# cheapboard1_0.net
KiCad netlist of a schematic drawn in EAGLE
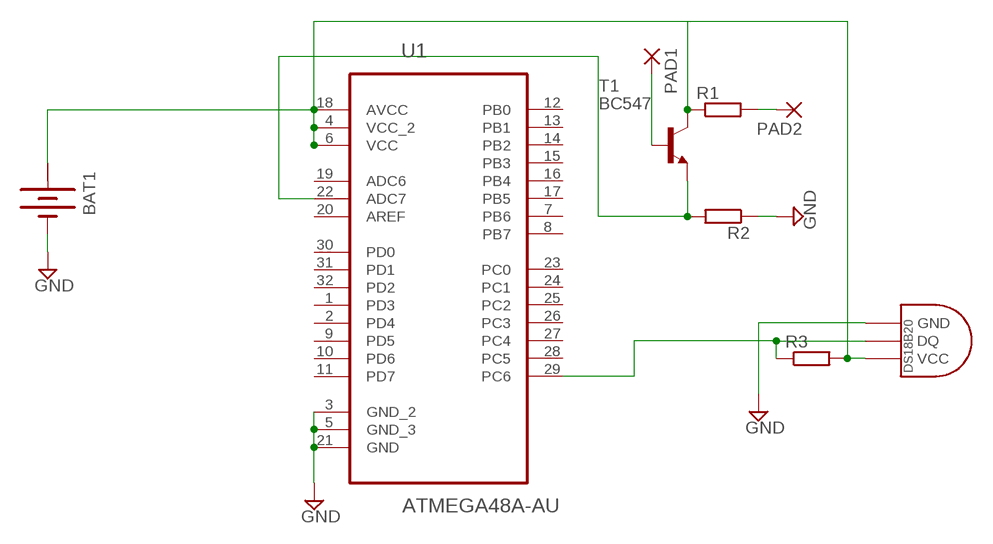
[diagram p0: schematic, sheet 1]

(export (version "E")
  (design (tool "Eeschema 10.0.6"))
  (components
    (comp (ref "BAT1")
      (value "BATTERY")
      (footprint "eagle-import:BATTERY")
      (libsource (lib "eagle-import") (part "BATTERY"))
    )
    (comp (ref "PAD1")
      (value "SMD5")
      (footprint "eagle-import:SMD2,54-5,08")
      (libsource (lib "eagle-import") (part "SMD5"))
    )
    (comp (ref "PAD2")
      (value "SMD5")
      (footprint "eagle-import:SMD2,54-5,08")
      (libsource (lib "eagle-import") (part "SMD5"))
    )
    (comp (ref "R1")
      (value "R-EU_M0805")
      (footprint "eagle-import:M0805")
      (libsource (lib "eagle-import") (part "R-EU_M0805"))
    )
    (comp (ref "R2")
      (value "R-EU_M0805")
      (footprint "eagle-import:M0805")
      (libsource (lib "eagle-import") (part "R-EU_M0805"))
    )
    (comp (ref "R3")
      (value "R-EU_M0805")
      (footprint "eagle-import:M0805")
      (libsource (lib "eagle-import") (part "R-EU_M0805"))
    )
    (comp (ref "T1")
      (value "BC547")
      (footprint "eagle-import:TO92")
      (libsource (lib "eagle-import") (part "BC547"))
    )
    (comp (ref "U$1")
      (value "DS1820SOIC")
      (footprint "eagle-import:DS18B20_SOIC")
      (libsource (lib "eagle-import") (part "DS1820SOIC"))
    )
    (comp (ref "U1")
      (value "ATMEGA48A-AU")
      (footprint "eagle-import:QFP80P900X900X120-32N")
      (libsource (lib "eagle-import") (part "ATMEGA48A-AU"))
    )
  )
  (nets
    (net (code "1") (name "/+") (class "Default")
      (node (ref "BAT1") (pin "+@1") (pinfunction "+_+@1") (pintype "power_in"))
    )
    (net (code "2") (name "GND") (class "Default")
      (node (ref "BAT1") (pin "-") (pinfunction "-_-") (pintype "power_in"))
      (node (ref "R2") (pin "1") (pinfunction "1_1") (pintype "passive"))
      (node (ref "U$1") (pin "GND") (pinfunction "GND_GND") (pintype "power_in"))
      (node (ref "U1") (pin "21") (pinfunction "GND_21") (pintype "passive"))
      (node (ref "U1") (pin "3") (pinfunction "GND_2_3") (pintype "passive"))
      (node (ref "U1") (pin "5") (pinfunction "GND_3_5") (pintype "passive"))
    )
    (net (code "3") (name "Net-(PAD1-P)") (class "Default")
      (node (ref "PAD1") (pin "1") (pinfunction "P_1") (pintype "passive"))
      (node (ref "T1") (pin "2") (pinfunction "B_2") (pintype "passive"))
    )
    (net (code "4") (name "Net-(PAD2-P)") (class "Default")
      (node (ref "PAD2") (pin "1") (pinfunction "P_1") (pintype "passive"))
      (node (ref "R1") (pin "2") (pinfunction "2_2") (pintype "passive"))
    )
    (net (code "5") (name "Net-(T1-C)") (class "Default")
      (node (ref "BAT1") (pin "+") (pinfunction "+_+") (pintype "power_in"))
      (node (ref "R1") (pin "1") (pinfunction "1_1") (pintype "passive"))
      (node (ref "R3") (pin "2") (pinfunction "2_2") (pintype "passive"))
      (node (ref "T1") (pin "3") (pinfunction "C_3") (pintype "passive"))
      (node (ref "U$1") (pin "VCC") (pinfunction "VCC_VCC") (pintype "power_in"))
      (node (ref "U1") (pin "18") (pinfunction "AVCC_18") (pintype "power_in"))
      (node (ref "U1") (pin "4") (pinfunction "VCC_2_4") (pintype "power_in"))
      (node (ref "U1") (pin "6") (pinfunction "VCC_6") (pintype "power_in"))
    )
    (net (code "6") (name "Net-(T1-E)") (class "Default")
      (node (ref "R2") (pin "2") (pinfunction "2_2") (pintype "passive"))
      (node (ref "T1") (pin "1") (pinfunction "E_1") (pintype "passive"))
      (node (ref "U1") (pin "22") (pinfunction "ADC7_22") (pintype "input"))
    )
    (net (code "7") (name "Net-(U1-PC6)") (class "Default")
      (node (ref "R3") (pin "1") (pinfunction "1_1") (pintype "passive"))
      (node (ref "U$1") (pin "DQ") (pinfunction "DQ_DQ") (pintype "bidirectional"))
      (node (ref "U1") (pin "29") (pinfunction "PC6_29") (pintype "bidirectional"))
    )
    (net (code "8") (name "unconnected-(U1-ADC6-Pad19)") (class "Default")
      (node (ref "U1") (pin "19") (pinfunction "ADC6_19") (pintype "input"))
    )
    (net (code "9") (name "unconnected-(U1-AREF-Pad20)") (class "Default")
      (node (ref "U1") (pin "20") (pinfunction "AREF_20") (pintype "input"))
    )
    (net (code "10") (name "unconnected-(U1-PB0-Pad12)") (class "Default")
      (node (ref "U1") (pin "12") (pinfunction "PB0_12") (pintype "bidirectional"))
    )
    (net (code "11") (name "unconnected-(U1-PB1-Pad13)") (class "Default")
      (node (ref "U1") (pin "13") (pinfunction "PB1_13") (pintype "bidirectional"))
    )
    (net (code "12") (name "unconnected-(U1-PB2-Pad14)") (class "Default")
      (node (ref "U1") (pin "14") (pinfunction "PB2_14") (pintype "bidirectional"))
    )
    (net (code "13") (name "unconnected-(U1-PB3-Pad15)") (class "Default")
      (node (ref "U1") (pin "15") (pinfunction "PB3_15") (pintype "bidirectional"))
    )
    (net (code "14") (name "unconnected-(U1-PB4-Pad16)") (class "Default")
      (node (ref "U1") (pin "16") (pinfunction "PB4_16") (pintype "bidirectional"))
    )
    (net (code "15") (name "unconnected-(U1-PB5-Pad17)") (class "Default")
      (node (ref "U1") (pin "17") (pinfunction "PB5_17") (pintype "bidirectional"))
    )
    (net (code "16") (name "unconnected-(U1-PB6-Pad7)") (class "Default")
      (node (ref "U1") (pin "7") (pinfunction "PB6_7") (pintype "bidirectional"))
    )
    (net (code "17") (name "unconnected-(U1-PB7-Pad8)") (class "Default")
      (node (ref "U1") (pin "8") (pinfunction "PB7_8") (pintype "bidirectional"))
    )
    (net (code "18") (name "unconnected-(U1-PC0-Pad23)") (class "Default")
      (node (ref "U1") (pin "23") (pinfunction "PC0_23") (pintype "bidirectional"))
    )
    (net (code "19") (name "unconnected-(U1-PC1-Pad24)") (class "Default")
      (node (ref "U1") (pin "24") (pinfunction "PC1_24") (pintype "bidirectional"))
    )
    (net (code "20") (name "unconnected-(U1-PC2-Pad25)") (class "Default")
      (node (ref "U1") (pin "25") (pinfunction "PC2_25") (pintype "bidirectional"))
    )
    (net (code "21") (name "unconnected-(U1-PC3-Pad26)") (class "Default")
      (node (ref "U1") (pin "26") (pinfunction "PC3_26") (pintype "bidirectional"))
    )
    (net (code "22") (name "unconnected-(U1-PC4-Pad27)") (class "Default")
      (node (ref "U1") (pin "27") (pinfunction "PC4_27") (pintype "bidirectional"))
    )
    (net (code "23") (name "unconnected-(U1-PC5-Pad28)") (class "Default")
      (node (ref "U1") (pin "28") (pinfunction "PC5_28") (pintype "bidirectional"))
    )
    (net (code "24") (name "unconnected-(U1-PD0-Pad30)") (class "Default")
      (node (ref "U1") (pin "30") (pinfunction "PD0_30") (pintype "bidirectional"))
    )
    (net (code "25") (name "unconnected-(U1-PD1-Pad31)") (class "Default")
      (node (ref "U1") (pin "31") (pinfunction "PD1_31") (pintype "bidirectional"))
    )
    (net (code "26") (name "unconnected-(U1-PD2-Pad32)") (class "Default")
      (node (ref "U1") (pin "32") (pinfunction "PD2_32") (pintype "bidirectional"))
    )
    (net (code "27") (name "unconnected-(U1-PD3-Pad1)") (class "Default")
      (node (ref "U1") (pin "1") (pinfunction "PD3_1") (pintype "bidirectional"))
    )
    (net (code "28") (name "unconnected-(U1-PD4-Pad2)") (class "Default")
      (node (ref "U1") (pin "2") (pinfunction "PD4_2") (pintype "bidirectional"))
    )
    (net (code "29") (name "unconnected-(U1-PD5-Pad9)") (class "Default")
      (node (ref "U1") (pin "9") (pinfunction "PD5_9") (pintype "bidirectional"))
    )
    (net (code "30") (name "unconnected-(U1-PD6-Pad10)") (class "Default")
      (node (ref "U1") (pin "10") (pinfunction "PD6_10") (pintype "bidirectional"))
    )
    (net (code "31") (name "unconnected-(U1-PD7-Pad11)") (class "Default")
      (node (ref "U1") (pin "11") (pinfunction "PD7_11") (pintype "bidirectional"))
    )
  )
)
